# Precision_ATMega32U4_Copernicus.net
KiCad netlist of a schematic drawn in EAGLE
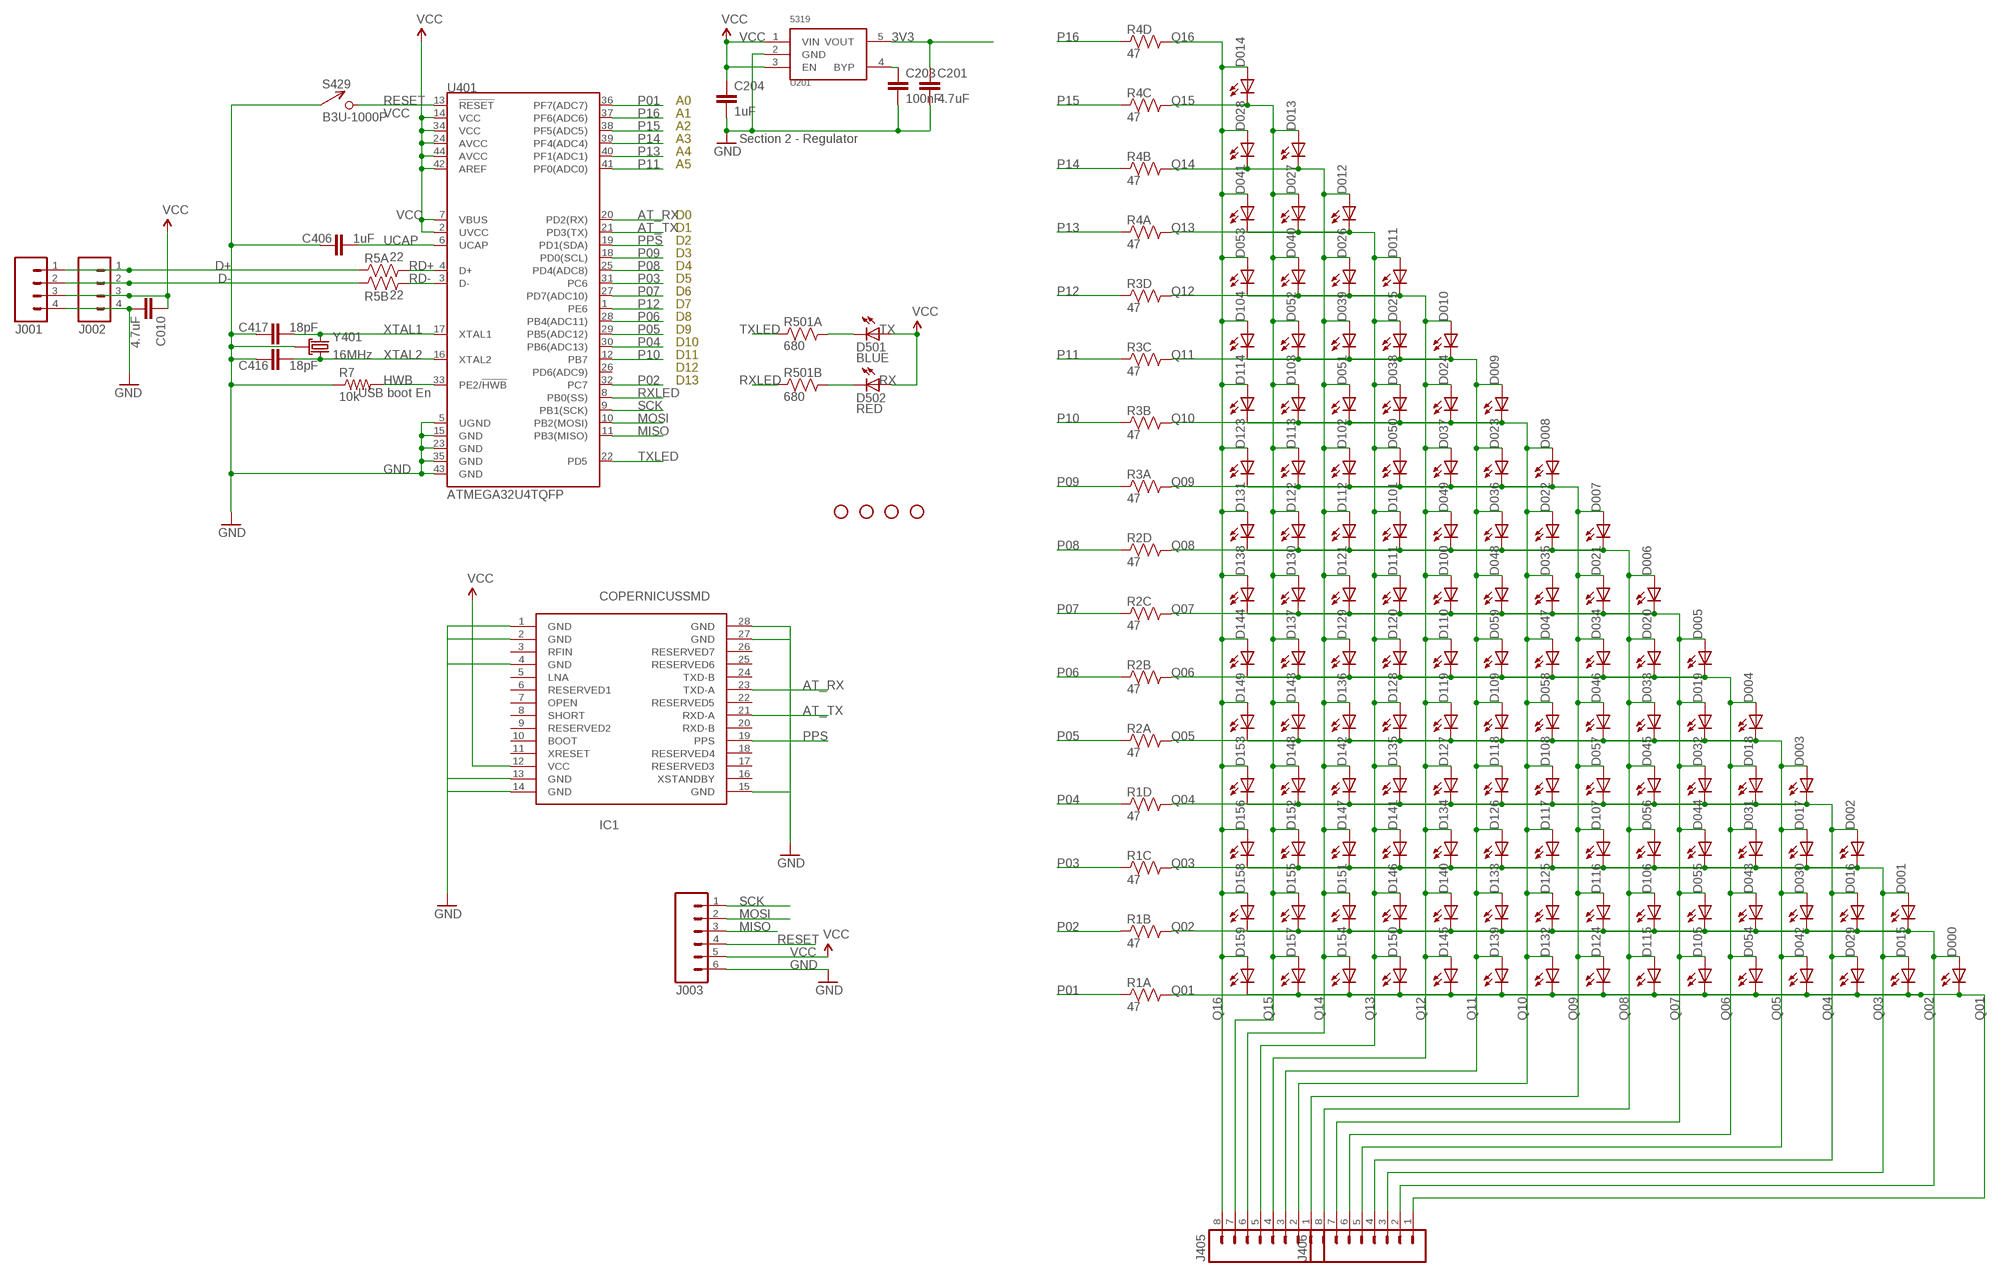
[diagram p0: schematic, sheet 1]

(export (version "E")
  (design (tool "Eeschema 10.0.6"))
  (components
    (comp (ref "C010")
      (value "4.7uF")
      (footprint "eagle-import:0603-CAP")
      (libsource (lib "eagle-import") (part "CAP0603-CAP"))
    )
    (comp (ref "C201")
      (value "4.7uF")
      (footprint "eagle-import:0402-CAP")
      (libsource (lib "eagle-import") (part "CAP0402-CAP"))
    )
    (comp (ref "C203")
      (value "100nF")
      (footprint "eagle-import:0402-CAP")
      (libsource (lib "eagle-import") (part "CAP0402-CAP"))
    )
    (comp (ref "C204")
      (value "1uF")
      (footprint "eagle-import:0402-CAP")
      (libsource (lib "eagle-import") (part "CAP0402-CAP"))
    )
    (comp (ref "C406")
      (value "1uF")
      (footprint "eagle-import:0603-CAP")
      (libsource (lib "eagle-import") (part "CAP0603-CAP"))
    )
    (comp (ref "C416")
      (value "18pF")
      (footprint "eagle-import:0603-CAP")
      (libsource (lib "eagle-import") (part "CAP0603-CAP"))
    )
    (comp (ref "C417")
      (value "18pF")
      (footprint "eagle-import:0603-CAP")
      (libsource (lib "eagle-import") (part "CAP0603-CAP"))
    )
    (comp (ref "D000")
      (value "HOUR")
      (footprint "eagle-import:LED-0603")
      (libsource (lib "eagle-import") (part "LED0603"))
    )
    (comp (ref "D001")
      (value "HOUR")
      (footprint "eagle-import:LED-0603")
      (libsource (lib "eagle-import") (part "LED0603"))
    )
    (comp (ref "D002")
      (value "HOUR")
      (footprint "eagle-import:LED-0603")
      (libsource (lib "eagle-import") (part "LED0603"))
    )
    (comp (ref "D003")
      (value "HOUR")
      (footprint "eagle-import:LED-0603")
      (libsource (lib "eagle-import") (part "LED0603"))
    )
    (comp (ref "D004")
      (value "HOUR")
      (footprint "eagle-import:LED-0603")
      (libsource (lib "eagle-import") (part "LED0603"))
    )
    (comp (ref "D005")
      (value "HOUR")
      (footprint "eagle-import:LED-0603")
      (libsource (lib "eagle-import") (part "LED0603"))
    )
    (comp (ref "D006")
      (value "HOUR")
      (footprint "eagle-import:LED-0603")
      (libsource (lib "eagle-import") (part "LED0603"))
    )
    (comp (ref "D007")
      (value "HOUR")
      (footprint "eagle-import:LED-0603")
      (libsource (lib "eagle-import") (part "LED0603"))
    )
    (comp (ref "D008")
      (value "HOUR")
      (footprint "eagle-import:LED-0603")
      (libsource (lib "eagle-import") (part "LED0603"))
    )
    (comp (ref "D009")
      (value "HOUR")
      (footprint "eagle-import:LED-0603")
      (libsource (lib "eagle-import") (part "LED0603"))
    )
    (comp (ref "D010")
      (value "HOUR")
      (footprint "eagle-import:LED-0603")
      (libsource (lib "eagle-import") (part "LED0603"))
    )
    (comp (ref "D011")
      (value "HOUR")
      (footprint "eagle-import:LED-0603")
      (libsource (lib "eagle-import") (part "LED0603"))
    )
    (comp (ref "D012")
      (value "HOUR")
      (footprint "eagle-import:LED-0603")
      (libsource (lib "eagle-import") (part "LED0603"))
    )
    (comp (ref "D013")
      (value "HOUR")
      (footprint "eagle-import:LED-0603")
      (libsource (lib "eagle-import") (part "LED0603"))
    )
    (comp (ref "D014")
      (value "HOUR")
      (footprint "eagle-import:LED-0603")
      (libsource (lib "eagle-import") (part "LED0603"))
    )
    (comp (ref "D015")
      (value "HOUR")
      (footprint "eagle-import:LED-0603")
      (libsource (lib "eagle-import") (part "LED0603"))
    )
    (comp (ref "D016")
      (value "HOUR")
      (footprint "eagle-import:LED-0603")
      (libsource (lib "eagle-import") (part "LED0603"))
    )
    (comp (ref "D017")
      (value "HOUR")
      (footprint "eagle-import:LED-0603")
      (libsource (lib "eagle-import") (part "LED0603"))
    )
    (comp (ref "D018")
      (value "HOUR")
      (footprint "eagle-import:LED-0603")
      (libsource (lib "eagle-import") (part "LED0603"))
    )
    (comp (ref "D019")
      (value "HOUR")
      (footprint "eagle-import:LED-0603")
      (libsource (lib "eagle-import") (part "LED0603"))
    )
    (comp (ref "D020")
      (value "HOUR")
      (footprint "eagle-import:LED-0603")
      (libsource (lib "eagle-import") (part "LED0603"))
    )
    (comp (ref "D021")
      (value "HOUR")
      (footprint "eagle-import:LED-0603")
      (libsource (lib "eagle-import") (part "LED0603"))
    )
    (comp (ref "D022")
      (value "HOUR")
      (footprint "eagle-import:LED-0603")
      (libsource (lib "eagle-import") (part "LED0603"))
    )
    (comp (ref "D023")
      (value "HOUR")
      (footprint "eagle-import:LED-0603")
      (libsource (lib "eagle-import") (part "LED0603"))
    )
    (comp (ref "D024")
      (value "HOUR")
      (footprint "eagle-import:LED-0603")
      (libsource (lib "eagle-import") (part "LED0603"))
    )
    (comp (ref "D025")
      (value "HOUR")
      (footprint "eagle-import:LED-0603")
      (libsource (lib "eagle-import") (part "LED0603"))
    )
    (comp (ref "D026")
      (value "HOUR")
      (footprint "eagle-import:LED-0603")
      (libsource (lib "eagle-import") (part "LED0603"))
    )
    (comp (ref "D027")
      (value "HOUR")
      (footprint "eagle-import:LED-0603")
      (libsource (lib "eagle-import") (part "LED0603"))
    )
    (comp (ref "D028")
      (value "HOUR")
      (footprint "eagle-import:LED-0603")
      (libsource (lib "eagle-import") (part "LED0603"))
    )
    (comp (ref "D029")
      (value "HOUR")
      (footprint "eagle-import:LED-0603")
      (libsource (lib "eagle-import") (part "LED0603"))
    )
    (comp (ref "D030")
      (value "HOUR")
      (footprint "eagle-import:LED-0603")
      (libsource (lib "eagle-import") (part "LED0603"))
    )
    (comp (ref "D031")
      (value "HOUR")
      (footprint "eagle-import:LED-0603")
      (libsource (lib "eagle-import") (part "LED0603"))
    )
    (comp (ref "D032")
      (value "HOUR")
      (footprint "eagle-import:LED-0603")
      (libsource (lib "eagle-import") (part "LED0603"))
    )
    (comp (ref "D033")
      (value "HOUR")
      (footprint "eagle-import:LED-0603")
      (libsource (lib "eagle-import") (part "LED0603"))
    )
    (comp (ref "D034")
      (value "HOUR")
      (footprint "eagle-import:LED-0603")
      (libsource (lib "eagle-import") (part "LED0603"))
    )
    (comp (ref "D035")
      (value "HOUR")
      (footprint "eagle-import:LED-0603")
      (libsource (lib "eagle-import") (part "LED0603"))
    )
    (comp (ref "D036")
      (value "HOUR")
      (footprint "eagle-import:LED-0603")
      (libsource (lib "eagle-import") (part "LED0603"))
    )
    (comp (ref "D037")
      (value "HOUR")
      (footprint "eagle-import:LED-0603")
      (libsource (lib "eagle-import") (part "LED0603"))
    )
    (comp (ref "D038")
      (value "HOUR")
      (footprint "eagle-import:LED-0603")
      (libsource (lib "eagle-import") (part "LED0603"))
    )
    (comp (ref "D039")
      (value "HOUR")
      (footprint "eagle-import:LED-0603")
      (libsource (lib "eagle-import") (part "LED0603"))
    )
    (comp (ref "D040")
      (value "HOUR")
      (footprint "eagle-import:LED-0603")
      (libsource (lib "eagle-import") (part "LED0603"))
    )
    (comp (ref "D041")
      (value "HOUR")
      (footprint "eagle-import:LED-0603")
      (libsource (lib "eagle-import") (part "LED0603"))
    )
    (comp (ref "D042")
      (value "HOUR")
      (footprint "eagle-import:LED-0603")
      (libsource (lib "eagle-import") (part "LED0603"))
    )
    (comp (ref "D043")
      (value "HOUR")
      (footprint "eagle-import:LED-0603")
      (libsource (lib "eagle-import") (part "LED0603"))
    )
    (comp (ref "D044")
      (value "HOUR")
      (footprint "eagle-import:LED-0603")
      (libsource (lib "eagle-import") (part "LED0603"))
    )
    (comp (ref "D045")
      (value "HOUR")
      (footprint "eagle-import:LED-0603")
      (libsource (lib "eagle-import") (part "LED0603"))
    )
    (comp (ref "D046")
      (value "HOUR")
      (footprint "eagle-import:LED-0603")
      (libsource (lib "eagle-import") (part "LED0603"))
    )
    (comp (ref "D047")
      (value "HOUR")
      (footprint "eagle-import:LED-0603")
      (libsource (lib "eagle-import") (part "LED0603"))
    )
    (comp (ref "D048")
      (value "HOUR")
      (footprint "eagle-import:LED-0603")
      (libsource (lib "eagle-import") (part "LED0603"))
    )
    (comp (ref "D049")
      (value "HOUR")
      (footprint "eagle-import:LED-0603")
      (libsource (lib "eagle-import") (part "LED0603"))
    )
    (comp (ref "D050")
      (value "HOUR")
      (footprint "eagle-import:LED-0603")
      (libsource (lib "eagle-import") (part "LED0603"))
    )
    (comp (ref "D051")
      (value "HOUR")
      (footprint "eagle-import:LED-0603")
      (libsource (lib "eagle-import") (part "LED0603"))
    )
    (comp (ref "D052")
      (value "HOUR")
      (footprint "eagle-import:LED-0603")
      (libsource (lib "eagle-import") (part "LED0603"))
    )
    (comp (ref "D053")
      (value "HOUR")
      (footprint "eagle-import:LED-0603")
      (libsource (lib "eagle-import") (part "LED0603"))
    )
    (comp (ref "D054")
      (value "HOUR")
      (footprint "eagle-import:LED-0603")
      (libsource (lib "eagle-import") (part "LED0603"))
    )
    (comp (ref "D055")
      (value "HOUR")
      (footprint "eagle-import:LED-0603")
      (libsource (lib "eagle-import") (part "LED0603"))
    )
    (comp (ref "D056")
      (value "HOUR")
      (footprint "eagle-import:LED-0603")
      (libsource (lib "eagle-import") (part "LED0603"))
    )
    (comp (ref "D057")
      (value "HOUR")
      (footprint "eagle-import:LED-0603")
      (libsource (lib "eagle-import") (part "LED0603"))
    )
    (comp (ref "D058")
      (value "HOUR")
      (footprint "eagle-import:LED-0603")
      (libsource (lib "eagle-import") (part "LED0603"))
    )
    (comp (ref "D059")
      (value "HOUR")
      (footprint "eagle-import:LED-0603")
      (libsource (lib "eagle-import") (part "LED0603"))
    )
    (comp (ref "D100")
      (value "HOUR")
      (footprint "eagle-import:LED-0603")
      (libsource (lib "eagle-import") (part "LED0603"))
    )
    (comp (ref "D101")
      (value "HOUR")
      (footprint "eagle-import:LED-0603")
      (libsource (lib "eagle-import") (part "LED0603"))
    )
    (comp (ref "D102")
      (value "HOUR")
      (footprint "eagle-import:LED-0603")
      (libsource (lib "eagle-import") (part "LED0603"))
    )
    (comp (ref "D103")
      (value "HOUR")
      (footprint "eagle-import:LED-0603")
      (libsource (lib "eagle-import") (part "LED0603"))
    )
    (comp (ref "D104")
      (value "HOUR")
      (footprint "eagle-import:LED-0603")
      (libsource (lib "eagle-import") (part "LED0603"))
    )
    (comp (ref "D105")
      (value "HOUR")
      (footprint "eagle-import:LED-0603")
      (libsource (lib "eagle-import") (part "LED0603"))
    )
    (comp (ref "D106")
      (value "HOUR")
      (footprint "eagle-import:LED-0603")
      (libsource (lib "eagle-import") (part "LED0603"))
    )
    (comp (ref "D107")
      (value "HOUR")
      (footprint "eagle-import:LED-0603")
      (libsource (lib "eagle-import") (part "LED0603"))
    )
    (comp (ref "D108")
      (value "HOUR")
      (footprint "eagle-import:LED-0603")
      (libsource (lib "eagle-import") (part "LED0603"))
    )
    (comp (ref "D109")
      (value "HOUR")
      (footprint "eagle-import:LED-0603")
      (libsource (lib "eagle-import") (part "LED0603"))
    )
    (comp (ref "D110")
      (value "HOUR")
      (footprint "eagle-import:LED-0603")
      (libsource (lib "eagle-import") (part "LED0603"))
    )
    (comp (ref "D111")
      (value "HOUR")
      (footprint "eagle-import:LED-0603")
      (libsource (lib "eagle-import") (part "LED0603"))
    )
    (comp (ref "D112")
      (value "HOUR")
      (footprint "eagle-import:LED-0603")
      (libsource (lib "eagle-import") (part "LED0603"))
    )
    (comp (ref "D113")
      (value "HOUR")
      (footprint "eagle-import:LED-0603")
      (libsource (lib "eagle-import") (part "LED0603"))
    )
    (comp (ref "D114")
      (value "HOUR")
      (footprint "eagle-import:LED-0603")
      (libsource (lib "eagle-import") (part "LED0603"))
    )
    (comp (ref "D115")
      (value "HOUR")
      (footprint "eagle-import:LED-0603")
      (libsource (lib "eagle-import") (part "LED0603"))
    )
    (comp (ref "D116")
      (value "HOUR")
      (footprint "eagle-import:LED-0603")
      (libsource (lib "eagle-import") (part "LED0603"))
    )
    (comp (ref "D117")
      (value "HOUR")
      (footprint "eagle-import:LED-0603")
      (libsource (lib "eagle-import") (part "LED0603"))
    )
    (comp (ref "D118")
      (value "HOUR")
      (footprint "eagle-import:LED-0603")
      (libsource (lib "eagle-import") (part "LED0603"))
    )
    (comp (ref "D119")
      (value "HOUR")
      (footprint "eagle-import:LED-0603")
      (libsource (lib "eagle-import") (part "LED0603"))
    )
    (comp (ref "D120")
      (value "HOUR")
      (footprint "eagle-import:LED-0603")
      (libsource (lib "eagle-import") (part "LED0603"))
    )
    (comp (ref "D121")
      (value "HOUR")
      (footprint "eagle-import:LED-0603")
      (libsource (lib "eagle-import") (part "LED0603"))
    )
    (comp (ref "D122")
      (value "HOUR")
      (footprint "eagle-import:LED-0603")
      (libsource (lib "eagle-import") (part "LED0603"))
    )
    (comp (ref "D123")
      (value "HOUR")
      (footprint "eagle-import:LED-0603")
      (libsource (lib "eagle-import") (part "LED0603"))
    )
    (comp (ref "D124")
      (value "HOUR")
      (footprint "eagle-import:LED-0603")
      (libsource (lib "eagle-import") (part "LED0603"))
    )
    (comp (ref "D125")
      (value "HOUR")
      (footprint "eagle-import:LED-0603")
      (libsource (lib "eagle-import") (part "LED0603"))
    )
    (comp (ref "D126")
      (value "HOUR")
      (footprint "eagle-import:LED-0603")
      (libsource (lib "eagle-import") (part "LED0603"))
    )
    (comp (ref "D127")
      (value "HOUR")
      (footprint "eagle-import:LED-0603")
      (libsource (lib "eagle-import") (part "LED0603"))
    )
    (comp (ref "D128")
      (value "HOUR")
      (footprint "eagle-import:LED-0603")
      (libsource (lib "eagle-import") (part "LED0603"))
    )
    (comp (ref "D129")
      (value "HOUR")
      (footprint "eagle-import:LED-0603")
      (libsource (lib "eagle-import") (part "LED0603"))
    )
    (comp (ref "D130")
      (value "HOUR")
      (footprint "eagle-import:LED-0603")
      (libsource (lib "eagle-import") (part "LED0603"))
    )
    (comp (ref "D131")
      (value "HOUR")
      (footprint "eagle-import:LED-0603")
      (libsource (lib "eagle-import") (part "LED0603"))
    )
    (comp (ref "D132")
      (value "HOUR")
      (footprint "eagle-import:LED-0603")
      (libsource (lib "eagle-import") (part "LED0603"))
    )
    (comp (ref "D133")
      (value "HOUR")
      (footprint "eagle-import:LED-0603")
      (libsource (lib "eagle-import") (part "LED0603"))
    )
    (comp (ref "D134")
      (value "HOUR")
      (footprint "eagle-import:LED-0603")
      (libsource (lib "eagle-import") (part "LED0603"))
    )
    (comp (ref "D135")
      (value "HOUR")
      (footprint "eagle-import:LED-0603")
      (libsource (lib "eagle-import") (part "LED0603"))
    )
    (comp (ref "D136")
      (value "HOUR")
      (footprint "eagle-import:LED-0603")
      (libsource (lib "eagle-import") (part "LED0603"))
    )
    (comp (ref "D137")
      (value "HOUR")
      (footprint "eagle-import:LED-0603")
      (libsource (lib "eagle-import") (part "LED0603"))
    )
    (comp (ref "D138")
      (value "HOUR")
      (footprint "eagle-import:LED-0603")
      (libsource (lib "eagle-import") (part "LED0603"))
    )
    (comp (ref "D139")
      (value "HOUR")
      (footprint "eagle-import:LED-0603")
      (libsource (lib "eagle-import") (part "LED0603"))
    )
    (comp (ref "D140")
      (value "HOUR")
      (footprint "eagle-import:LED-0603")
      (libsource (lib "eagle-import") (part "LED0603"))
    )
    (comp (ref "D141")
      (value "HOUR")
      (footprint "eagle-import:LED-0603")
      (libsource (lib "eagle-import") (part "LED0603"))
    )
    (comp (ref "D142")
      (value "HOUR")
      (footprint "eagle-import:LED-0603")
      (libsource (lib "eagle-import") (part "LED0603"))
    )
    (comp (ref "D143")
      (value "HOUR")
      (footprint "eagle-import:LED-0603")
      (libsource (lib "eagle-import") (part "LED0603"))
    )
    (comp (ref "D144")
      (value "HOUR")
      (footprint "eagle-import:LED-0603")
      (libsource (lib "eagle-import") (part "LED0603"))
    )
    (comp (ref "D145")
      (value "HOUR")
      (footprint "eagle-import:LED-0603")
      (libsource (lib "eagle-import") (part "LED0603"))
    )
    (comp (ref "D146")
      (value "HOUR")
      (footprint "eagle-import:LED-0603")
      (libsource (lib "eagle-import") (part "LED0603"))
    )
    (comp (ref "D147")
      (value "HOUR")
      (footprint "eagle-import:LED-0603")
      (libsource (lib "eagle-import") (part "LED0603"))
    )
    (comp (ref "D148")
      (value "HOUR")
      (footprint "eagle-import:LED-0603")
      (libsource (lib "eagle-import") (part "LED0603"))
    )
    (comp (ref "D149")
      (value "HOUR")
      (footprint "eagle-import:LED-0603")
      (libsource (lib "eagle-import") (part "LED0603"))
    )
    (comp (ref "D150")
      (value "HOUR")
      (footprint "eagle-import:LED-0603")
      (libsource (lib "eagle-import") (part "LED0603"))
    )
    (comp (ref "D151")
      (value "HOUR")
      (footprint "eagle-import:LED-0603")
      (libsource (lib "eagle-import") (part "LED0603"))
    )
    (comp (ref "D152")
      (value "HOUR")
      (footprint "eagle-import:LED-0603")
      (libsource (lib "eagle-import") (part "LED0603"))
    )
    (comp (ref "D153")
      (value "HOUR")
      (footprint "eagle-import:LED-0603")
      (libsource (lib "eagle-import") (part "LED0603"))
    )
    (comp (ref "D154")
      (value "HOUR")
      (footprint "eagle-import:LED-0603")
      (libsource (lib "eagle-import") (part "LED0603"))
    )
    (comp (ref "D155")
      (value "HOUR")
      (footprint "eagle-import:LED-0603")
      (libsource (lib "eagle-import") (part "LED0603"))
    )
    (comp (ref "D156")
      (value "HOUR")
      (footprint "eagle-import:LED-0603")
      (libsource (lib "eagle-import") (part "LED0603"))
    )
    (comp (ref "D157")
      (value "HOUR")
      (footprint "eagle-import:LED-0603")
      (libsource (lib "eagle-import") (part "LED0603"))
    )
    (comp (ref "D158")
      (value "HOUR")
      (footprint "eagle-import:LED-0603")
      (libsource (lib "eagle-import") (part "LED0603"))
    )
    (comp (ref "D159")
      (value "HOUR")
      (footprint "eagle-import:LED-0603")
      (libsource (lib "eagle-import") (part "LED0603"))
    )
    (comp (ref "D501")
      (value "BLUE")
      (footprint "eagle-import:LED-0603")
      (libsource (lib "eagle-import") (part "LED0603"))
    )
    (comp (ref "D502")
      (value "RED")
      (footprint "eagle-import:LED-0603")
      (libsource (lib "eagle-import") (part "LED0603"))
    )
    (comp (ref "IC1")
      (value "COPERNICUSSMD")
      (footprint "eagle-import:COPERNICUS")
      (libsource (lib "eagle-import") (part "COPERNICUSSMD"))
    )
    (comp (ref "J001")
      (value "M04PTH")
      (footprint "eagle-import:1X04")
      (libsource (lib "eagle-import") (part "M04PTH"))
    )
    (comp (ref "J002")
      (value "M04PTH")
      (footprint "eagle-import:1X04")
      (libsource (lib "eagle-import") (part "M04PTH"))
    )
    (comp (ref "J003")
      (value "M06SIP")
      (footprint "eagle-import:1X06")
      (libsource (lib "eagle-import") (part "M06SIP"))
    )
    (comp (ref "J405")
      (value "M081X08")
      (footprint "eagle-import:1X08")
      (libsource (lib "eagle-import") (part "M081X08"))
    )
    (comp (ref "J406")
      (value "M081X08")
      (footprint "eagle-import:1X08")
      (libsource (lib "eagle-import") (part "M081X08"))
    )
    (comp (ref "JP1")
      (value "STAND-OFF")
      (footprint "eagle-import:STAND-OFF")
      (libsource (lib "eagle-import") (part "STAND-OFF"))
    )
    (comp (ref "JP2")
      (value "STAND-OFF")
      (footprint "eagle-import:STAND-OFF")
      (libsource (lib "eagle-import") (part "STAND-OFF"))
    )
    (comp (ref "JP3")
      (value "STAND-OFF")
      (footprint "eagle-import:STAND-OFF")
      (libsource (lib "eagle-import") (part "STAND-OFF"))
    )
    (comp (ref "JP4")
      (value "STAND-OFF")
      (footprint "eagle-import:STAND-OFF")
      (libsource (lib "eagle-import") (part "STAND-OFF"))
    )
    (comp (ref "R1")
      (value "47")
      (footprint "eagle-import:CRA04")
      (libsource (lib "eagle-import") (part "RP404"))
    )
    (comp (ref "R2")
      (value "47")
      (footprint "eagle-import:CRA04")
      (libsource (lib "eagle-import") (part "RP404"))
    )
    (comp (ref "R3")
      (value "47")
      (footprint "eagle-import:CRA04")
      (libsource (lib "eagle-import") (part "RP404"))
    )
    (comp (ref "R4")
      (value "47")
      (footprint "eagle-import:CRA04")
      (libsource (lib "eagle-import") (part "RP404"))
    )
    (comp (ref "R5")
      (value "22")
      (footprint "eagle-import:CRA02")
      (libsource (lib "eagle-import") (part "RP2EXB24V"))
    )
    (comp (ref "R7")
      (value "10k")
      (footprint "eagle-import:0603-RES")
      (libsource (lib "eagle-import") (part "RESISTOR0603-RES"))
    )
    (comp (ref "R501")
      (value "680")
      (footprint "eagle-import:CRA02")
      (libsource (lib "eagle-import") (part "RP2EXB24V"))
    )
    (comp (ref "S429")
      (value "B3U-1000P")
      (footprint "eagle-import:B3U-1000P")
      (libsource (lib "eagle-import") (part "B3U-1000P"))
    )
    (comp (ref "U201")
      (value "5319")
      (footprint "eagle-import:SOT-23-5")
      (libsource (lib "eagle-import") (part "MIC5319D5"))
    )
    (comp (ref "U401")
      (value "ATMEGA32U4TQFP")
      (footprint "eagle-import:SPARKFUN-DIGITALIC_TQFP44")
      (libsource (lib "eagle-import") (part "ATMEGA32U4TQFP"))
    )
    (comp (ref "Y401")
      (value "16MHz")
      (footprint "eagle-import:CRYSTAL_SMD")
      (libsource (lib "eagle-import") (part "TSX-3225"))
    )
  )
  (nets
    (net (code "1") (name "/3V3") (class "Default")
      (node (ref "C201") (pin "1") (pinfunction "1_1") (pintype "passive"))
      (node (ref "U201") (pin "5") (pinfunction "VOUT_5") (pintype "bidirectional"))
    )
    (net (code "2") (name "/AT_RX") (class "Default")
      (node (ref "IC1") (pin "23") (pinfunction "TXD-A_23") (pintype "bidirectional"))
      (node (ref "U401") (pin "20") (pinfunction "PD2(RX)_20") (pintype "bidirectional"))
    )
    (net (code "3") (name "/AT_TX") (class "Default")
      (node (ref "IC1") (pin "21") (pinfunction "RXD-A_21") (pintype "bidirectional"))
      (node (ref "U401") (pin "21") (pinfunction "PD3(TX)_21") (pintype "bidirectional"))
    )
    (net (code "4") (name "/D+") (class "Default")
      (node (ref "J001") (pin "1") (pinfunction "1_1") (pintype "passive"))
      (node (ref "J002") (pin "1") (pinfunction "1_1") (pintype "passive"))
      (node (ref "R5") (pin "1") (pinfunction "1_1") (pintype "passive"))
    )
    (net (code "5") (name "/D-") (class "Default")
      (node (ref "J001") (pin "2") (pinfunction "2_2") (pintype "passive"))
      (node (ref "J002") (pin "2") (pinfunction "2_2") (pintype "passive"))
      (node (ref "R5") (pin "2") (pinfunction "1_2") (pintype "passive"))
    )
    (net (code "6") (name "/HWB") (class "Default")
      (node (ref "R7") (pin "2") (pinfunction "2_2") (pintype "passive"))
      (node (ref "U401") (pin "33") (pinfunction "PE2/~{HWB}_33") (pintype "bidirectional"))
    )
    (net (code "7") (name "/MISO") (class "Default")
      (node (ref "J003") (pin "3") (pinfunction "3_3") (pintype "passive"))
      (node (ref "U401") (pin "11") (pinfunction "PB3(MISO)_11") (pintype "bidirectional"))
    )
    (net (code "8") (name "/MOSI") (class "Default")
      (node (ref "J003") (pin "2") (pinfunction "2_2") (pintype "passive"))
      (node (ref "U401") (pin "10") (pinfunction "PB2(MOSI)_10") (pintype "bidirectional"))
    )
    (net (code "9") (name "/P01") (class "Default")
      (node (ref "R1") (pin "1") (pinfunction "1_1") (pintype "passive"))
      (node (ref "U401") (pin "36") (pinfunction "PF7(ADC7)_36") (pintype "bidirectional"))
    )
    (net (code "10") (name "/P02") (class "Default")
      (node (ref "R1") (pin "2") (pinfunction "1_2") (pintype "passive"))
      (node (ref "U401") (pin "32") (pinfunction "PC7_32") (pintype "bidirectional"))
    )
    (net (code "11") (name "/P03") (class "Default")
      (node (ref "R1") (pin "3") (pinfunction "1_3") (pintype "passive"))
      (node (ref "U401") (pin "31") (pinfunction "PC6_31") (pintype "bidirectional"))
    )
    (net (code "12") (name "/P04") (class "Default")
      (node (ref "R1") (pin "4") (pinfunction "1_4") (pintype "passive"))
      (node (ref "U401") (pin "30") (pinfunction "PB6(ADC13)_30") (pintype "bidirectional"))
    )
    (net (code "13") (name "/P05") (class "Default")
      (node (ref "R2") (pin "1") (pinfunction "1_1") (pintype "passive"))
      (node (ref "U401") (pin "29") (pinfunction "PB5(ADC12)_29") (pintype "bidirectional"))
    )
    (net (code "14") (name "/P06") (class "Default")
      (node (ref "R2") (pin "2") (pinfunction "1_2") (pintype "passive"))
      (node (ref "U401") (pin "28") (pinfunction "PB4(ADC11)_28") (pintype "bidirectional"))
    )
    (net (code "15") (name "/P07") (class "Default")
      (node (ref "R2") (pin "3") (pinfunction "1_3") (pintype "passive"))
      (node (ref "U401") (pin "27") (pinfunction "PD7(ADC10)_27") (pintype "bidirectional"))
    )
    (net (code "16") (name "/P08") (class "Default")
      (node (ref "R2") (pin "4") (pinfunction "1_4") (pintype "passive"))
      (node (ref "U401") (pin "25") (pinfunction "PD4(ADC8)_25") (pintype "bidirectional"))
    )
    (net (code "17") (name "/P09") (class "Default")
      (node (ref "R3") (pin "1") (pinfunction "1_1") (pintype "passive"))
      (node (ref "U401") (pin "18") (pinfunction "PD0(SCL)_18") (pintype "bidirectional"))
    )
    (net (code "18") (name "/P10") (class "Default")
      (node (ref "R3") (pin "2") (pinfunction "1_2") (pintype "passive"))
      (node (ref "U401") (pin "12") (pinfunction "PB7_12") (pintype "bidirectional"))
    )
    (net (code "19") (name "/P11") (class "Default")
      (node (ref "R3") (pin "3") (pinfunction "1_3") (pintype "passive"))
      (node (ref "U401") (pin "41") (pinfunction "PF0(ADC0)_41") (pintype "bidirectional"))
    )
    (net (code "20") (name "/P12") (class "Default")
      (node (ref "R3") (pin "4") (pinfunction "1_4") (pintype "passive"))
      (node (ref "U401") (pin "1") (pinfunction "PE6_1") (pintype "bidirectional"))
    )
    (net (code "21") (name "/P13") (class "Default")
      (node (ref "R4") (pin "1") (pinfunction "1_1") (pintype "passive"))
      (node (ref "U401") (pin "40") (pinfunction "PF1(ADC1)_40") (pintype "bidirectional"))
    )
    (net (code "22") (name "/P14") (class "Default")
      (node (ref "R4") (pin "2") (pinfunction "1_2") (pintype "passive"))
      (node (ref "U401") (pin "39") (pinfunction "PF4(ADC4)_39") (pintype "bidirectional"))
    )
    (net (code "23") (name "/P15") (class "Default")
      (node (ref "R4") (pin "3") (pinfunction "1_3") (pintype "passive"))
      (node (ref "U401") (pin "38") (pinfunction "PF5(ADC5)_38") (pintype "bidirectional"))
    )
    (net (code "24") (name "/P16") (class "Default")
      (node (ref "R4") (pin "4") (pinfunction "1_4") (pintype "passive"))
      (node (ref "U401") (pin "37") (pinfunction "PF6(ADC6)_37") (pintype "bidirectional"))
    )
    (net (code "25") (name "/PPS") (class "Default")
      (node (ref "IC1") (pin "19") (pinfunction "PPS_19") (pintype "bidirectional"))
      (node (ref "U401") (pin "19") (pinfunction "PD1(SDA)_19") (pintype "bidirectional"))
    )
    (net (code "26") (name "/Q01") (class "Default")
      (node (ref "D000") (pin "C") (pinfunction "C_C") (pintype "passive"))
      (node (ref "D015") (pin "C") (pinfunction "C_C") (pintype "passive"))
      (node (ref "D029") (pin "C") (pinfunction "C_C") (pintype "passive"))
      (node (ref "D042") (pin "C") (pinfunction "C_C") (pintype "passive"))
      (node (ref "D054") (pin "C") (pinfunction "C_C") (pintype "passive"))
      (node (ref "D105") (pin "C") (pinfunction "C_C") (pintype "passive"))
      (node (ref "D115") (pin "C") (pinfunction "C_C") (pintype "passive"))
      (node (ref "D124") (pin "C") (pinfunction "C_C") (pintype "passive"))
      (node (ref "D132") (pin "C") (pinfunction "C_C") (pintype "passive"))
      (node (ref "D139") (pin "C") (pinfunction "C_C") (pintype "passive"))
      (node (ref "D145") (pin "C") (pinfunction "C_C") (pintype "passive"))
      (node (ref "D150") (pin "C") (pinfunction "C_C") (pintype "passive"))
      (node (ref "D154") (pin "C") (pinfunction "C_C") (pintype "passive"))
      (node (ref "D157") (pin "C") (pinfunction "C_C") (pintype "passive"))
      (node (ref "D159") (pin "C") (pinfunction "C_C") (pintype "passive"))
      (node (ref "J406") (pin "1") (pinfunction "1_1") (pintype "passive"))
      (node (ref "R1") (pin "8") (pinfunction "2_8") (pintype "passive"))
    )
    (net (code "27") (name "/Q02") (class "Default")
      (node (ref "D000") (pin "A") (pinfunction "A_A") (pintype "passive"))
      (node (ref "D001") (pin "C") (pinfunction "C_C") (pintype "passive"))
      (node (ref "D016") (pin "C") (pinfunction "C_C") (pintype "passive"))
      (node (ref "D030") (pin "C") (pinfunction "C_C") (pintype "passive"))
      (node (ref "D043") (pin "C") (pinfunction "C_C") (pintype "passive"))
      (node (ref "D055") (pin "C") (pinfunction "C_C") (pintype "passive"))
      (node (ref "D106") (pin "C") (pinfunction "C_C") (pintype "passive"))
      (node (ref "D116") (pin "C") (pinfunction "C_C") (pintype "passive"))
      (node (ref "D125") (pin "C") (pinfunction "C_C") (pintype "passive"))
      (node (ref "D133") (pin "C") (pinfunction "C_C") (pintype "passive"))
      (node (ref "D140") (pin "C") (pinfunction "C_C") (pintype "passive"))
      (node (ref "D146") (pin "C") (pinfunction "C_C") (pintype "passive"))
      (node (ref "D151") (pin "C") (pinfunction "C_C") (pintype "passive"))
      (node (ref "D155") (pin "C") (pinfunction "C_C") (pintype "passive"))
      (node (ref "D158") (pin "C") (pinfunction "C_C") (pintype "passive"))
      (node (ref "J406") (pin "2") (pinfunction "2_2") (pintype "passive"))
      (node (ref "R1") (pin "7") (pinfunction "2_7") (pintype "passive"))
    )
    (net (code "28") (name "/Q03") (class "Default")
      (node (ref "D001") (pin "A") (pinfunction "A_A") (pintype "passive"))
      (node (ref "D002") (pin "C") (pinfunction "C_C") (pintype "passive"))
      (node (ref "D015") (pin "A") (pinfunction "A_A") (pintype "passive"))
      (node (ref "D017") (pin "C") (pinfunction "C_C") (pintype "passive"))
      (node (ref "D031") (pin "C") (pinfunction "C_C") (pintype "passive"))
      (node (ref "D044") (pin "C") (pinfunction "C_C") (pintype "passive"))
      (node (ref "D056") (pin "C") (pinfunction "C_C") (pintype "passive"))
      (node (ref "D107") (pin "C") (pinfunction "C_C") (pintype "passive"))
      (node (ref "D117") (pin "C") (pinfunction "C_C") (pintype "passive"))
      (node (ref "D126") (pin "C") (pinfunction "C_C") (pintype "passive"))
      (node (ref "D134") (pin "C") (pinfunction "C_C") (pintype "passive"))
      (node (ref "D141") (pin "C") (pinfunction "C_C") (pintype "passive"))
      (node (ref "D147") (pin "C") (pinfunction "C_C") (pintype "passive"))
      (node (ref "D152") (pin "C") (pinfunction "C_C") (pintype "passive"))
      (node (ref "D156") (pin "C") (pinfunction "C_C") (pintype "passive"))
      (node (ref "J406") (pin "3") (pinfunction "3_3") (pintype "passive"))
      (node (ref "R1") (pin "6") (pinfunction "2_6") (pintype "passive"))
    )
    (net (code "29") (name "/Q04") (class "Default")
      (node (ref "D002") (pin "A") (pinfunction "A_A") (pintype "passive"))
      (node (ref "D003") (pin "C") (pinfunction "C_C") (pintype "passive"))
      (node (ref "D016") (pin "A") (pinfunction "A_A") (pintype "passive"))
      (node (ref "D018") (pin "C") (pinfunction "C_C") (pintype "passive"))
      (node (ref "D029") (pin "A") (pinfunction "A_A") (pintype "passive"))
      (node (ref "D032") (pin "C") (pinfunction "C_C") (pintype "passive"))
      (node (ref "D045") (pin "C") (pinfunction "C_C") (pintype "passive"))
      (node (ref "D057") (pin "C") (pinfunction "C_C") (pintype "passive"))
      (node (ref "D108") (pin "C") (pinfunction "C_C") (pintype "passive"))
      (node (ref "D118") (pin "C") (pinfunction "C_C") (pintype "passive"))
      (node (ref "D127") (pin "C") (pinfunction "C_C") (pintype "passive"))
      (node (ref "D135") (pin "C") (pinfunction "C_C") (pintype "passive"))
      (node (ref "D142") (pin "C") (pinfunction "C_C") (pintype "passive"))
      (node (ref "D148") (pin "C") (pinfunction "C_C") (pintype "passive"))
      (node (ref "D153") (pin "C") (pinfunction "C_C") (pintype "passive"))
      (node (ref "J406") (pin "4") (pinfunction "4_4") (pintype "passive"))
      (node (ref "R1") (pin "5") (pinfunction "2_5") (pintype "passive"))
    )
    (net (code "30") (name "/Q05") (class "Default")
      (node (ref "D003") (pin "A") (pinfunction "A_A") (pintype "passive"))
      (node (ref "D004") (pin "C") (pinfunction "C_C") (pintype "passive"))
      (node (ref "D017") (pin "A") (pinfunction "A_A") (pintype "passive"))
      (node (ref "D019") (pin "C") (pinfunction "C_C") (pintype "passive"))
      (node (ref "D030") (pin "A") (pinfunction "A_A") (pintype "passive"))
      (node (ref "D033") (pin "C") (pinfunction "C_C") (pintype "passive"))
      (node (ref "D042") (pin "A") (pinfunction "A_A") (pintype "passive"))
      (node (ref "D046") (pin "C") (pinfunction "C_C") (pintype "passive"))
      (node (ref "D058") (pin "C") (pinfunction "C_C") (pintype "passive"))
      (node (ref "D109") (pin "C") (pinfunction "C_C") (pintype "passive"))
      (node (ref "D119") (pin "C") (pinfunction "C_C") (pintype "passive"))
      (node (ref "D128") (pin "C") (pinfunction "C_C") (pintype "passive"))
      (node (ref "D136") (pin "C") (pinfunction "C_C") (pintype "passive"))
      (node (ref "D143") (pin "C") (pinfunction "C_C") (pintype "passive"))
      (node (ref "D149") (pin "C") (pinfunction "C_C") (pintype "passive"))
      (node (ref "J406") (pin "5") (pinfunction "5_5") (pintype "passive"))
      (node (ref "R2") (pin "8") (pinfunction "2_8") (pintype "passive"))
    )
    (net (code "31") (name "/Q06") (class "Default")
      (node (ref "D004") (pin "A") (pinfunction "A_A") (pintype "passive"))
      (node (ref "D005") (pin "C") (pinfunction "C_C") (pintype "passive"))
      (node (ref "D018") (pin "A") (pinfunction "A_A") (pintype "passive"))
      (node (ref "D020") (pin "C") (pinfunction "C_C") (pintype "passive"))
      (node (ref "D031") (pin "A") (pinfunction "A_A") (pintype "passive"))
      (node (ref "D034") (pin "C") (pinfunction "C_C") (pintype "passive"))
      (node (ref "D043") (pin "A") (pinfunction "A_A") (pintype "passive"))
      (node (ref "D047") (pin "C") (pinfunction "C_C") (pintype "passive"))
      (node (ref "D054") (pin "A") (pinfunction "A_A") (pintype "passive"))
      (node (ref "D059") (pin "C") (pinfunction "C_C") (pintype "passive"))
      (node (ref "D110") (pin "C") (pinfunction "C_C") (pintype "passive"))
      (node (ref "D120") (pin "C") (pinfunction "C_C") (pintype "passive"))
      (node (ref "D129") (pin "C") (pinfunction "C_C") (pintype "passive"))
      (node (ref "D137") (pin "C") (pinfunction "C_C") (pintype "passive"))
      (node (ref "D144") (pin "C") (pinfunction "C_C") (pintype "passive"))
      (node (ref "J406") (pin "6") (pinfunction "6_6") (pintype "passive"))
      (node (ref "R2") (pin "7") (pinfunction "2_7") (pintype "passive"))
    )
    (net (code "32") (name "/Q07") (class "Default")
      (node (ref "D005") (pin "A") (pinfunction "A_A") (pintype "passive"))
      (node (ref "D006") (pin "C") (pinfunction "C_C") (pintype "passive"))
      (node (ref "D019") (pin "A") (pinfunction "A_A") (pintype "passive"))
      (node (ref "D021") (pin "C") (pinfunction "C_C") (pintype "passive"))
      (node (ref "D032") (pin "A") (pinfunction "A_A") (pintype "passive"))
      (node (ref "D035") (pin "C") (pinfunction "C_C") (pintype "passive"))
      (node (ref "D044") (pin "A") (pinfunction "A_A") (pintype "passive"))
      (node (ref "D048") (pin "C") (pinfunction "C_C") (pintype "passive"))
      (node (ref "D055") (pin "A") (pinfunction "A_A") (pintype "passive"))
      (node (ref "D100") (pin "C") (pinfunction "C_C") (pintype "passive"))
      (node (ref "D105") (pin "A") (pinfunction "A_A") (pintype "passive"))
      (node (ref "D111") (pin "C") (pinfunction "C_C") (pintype "passive"))
      (node (ref "D121") (pin "C") (pinfunction "C_C") (pintype "passive"))
      (node (ref "D130") (pin "C") (pinfunction "C_C") (pintype "passive"))
      (node (ref "D138") (pin "C") (pinfunction "C_C") (pintype "passive"))
      (node (ref "J406") (pin "7") (pinfunction "7_7") (pintype "passive"))
      (node (ref "R2") (pin "6") (pinfunction "2_6") (pintype "passive"))
    )
    (net (code "33") (name "/Q08") (class "Default")
      (node (ref "D006") (pin "A") (pinfunction "A_A") (pintype "passive"))
      (node (ref "D007") (pin "C") (pinfunction "C_C") (pintype "passive"))
      (node (ref "D020") (pin "A") (pinfunction "A_A") (pintype "passive"))
      (node (ref "D022") (pin "C") (pinfunction "C_C") (pintype "passive"))
      (node (ref "D033") (pin "A") (pinfunction "A_A") (pintype "passive"))
      (node (ref "D036") (pin "C") (pinfunction "C_C") (pintype "passive"))
      (node (ref "D045") (pin "A") (pinfunction "A_A") (pintype "passive"))
      (node (ref "D049") (pin "C") (pinfunction "C_C") (pintype "passive"))
      (node (ref "D056") (pin "A") (pinfunction "A_A") (pintype "passive"))
      (node (ref "D101") (pin "C") (pinfunction "C_C") (pintype "passive"))
      (node (ref "D106") (pin "A") (pinfunction "A_A") (pintype "passive"))
      (node (ref "D112") (pin "C") (pinfunction "C_C") (pintype "passive"))
      (node (ref "D115") (pin "A") (pinfunction "A_A") (pintype "passive"))
      (node (ref "D122") (pin "C") (pinfunction "C_C") (pintype "passive"))
      (node (ref "D131") (pin "C") (pinfunction "C_C") (pintype "passive"))
      (node (ref "J406") (pin "8") (pinfunction "8_8") (pintype "passive"))
      (node (ref "R2") (pin "5") (pinfunction "2_5") (pintype "passive"))
    )
    (net (code "34") (name "/Q09") (class "Default")
      (node (ref "D007") (pin "A") (pinfunction "A_A") (pintype "passive"))
      (node (ref "D008") (pin "C") (pinfunction "C_C") (pintype "passive"))
      (node (ref "D021") (pin "A") (pinfunction "A_A") (pintype "passive"))
      (node (ref "D023") (pin "C") (pinfunction "C_C") (pintype "passive"))
      (node (ref "D034") (pin "A") (pinfunction "A_A") (pintype "passive"))
      (node (ref "D037") (pin "C") (pinfunction "C_C") (pintype "passive"))
      (node (ref "D046") (pin "A") (pinfunction "A_A") (pintype "passive"))
      (node (ref "D050") (pin "C") (pinfunction "C_C") (pintype "passive"))
      (node (ref "D057") (pin "A") (pinfunction "A_A") (pintype "passive"))
      (node (ref "D102") (pin "C") (pinfunction "C_C") (pintype "passive"))
      (node (ref "D107") (pin "A") (pinfunction "A_A") (pintype "passive"))
      (node (ref "D113") (pin "C") (pinfunction "C_C") (pintype "passive"))
      (node (ref "D116") (pin "A") (pinfunction "A_A") (pintype "passive"))
      (node (ref "D123") (pin "C") (pinfunction "C_C") (pintype "passive"))
      (node (ref "D124") (pin "A") (pinfunction "A_A") (pintype "passive"))
      (node (ref "J405") (pin "1") (pinfunction "1_1") (pintype "passive"))
      (node (ref "R3") (pin "8") (pinfunction "2_8") (pintype "passive"))
    )
    (net (code "35") (name "/Q10") (class "Default")
      (node (ref "D008") (pin "A") (pinfunction "A_A") (pintype "passive"))
      (node (ref "D009") (pin "C") (pinfunction "C_C") (pintype "passive"))
      (node (ref "D022") (pin "A") (pinfunction "A_A") (pintype "passive"))
      (node (ref "D024") (pin "C") (pinfunction "C_C") (pintype "passive"))
      (node (ref "D035") (pin "A") (pinfunction "A_A") (pintype "passive"))
      (node (ref "D038") (pin "C") (pinfunction "C_C") (pintype "passive"))
      (node (ref "D047") (pin "A") (pinfunction "A_A") (pintype "passive"))
      (node (ref "D051") (pin "C") (pinfunction "C_C") (pintype "passive"))
      (node (ref "D058") (pin "A") (pinfunction "A_A") (pintype "passive"))
      (node (ref "D103") (pin "C") (pinfunction "C_C") (pintype "passive"))
      (node (ref "D108") (pin "A") (pinfunction "A_A") (pintype "passive"))
      (node (ref "D114") (pin "C") (pinfunction "C_C") (pintype "passive"))
      (node (ref "D117") (pin "A") (pinfunction "A_A") (pintype "passive"))
      (node (ref "D125") (pin "A") (pinfunction "A_A") (pintype "passive"))
      (node (ref "D132") (pin "A") (pinfunction "A_A") (pintype "passive"))
      (node (ref "J405") (pin "2") (pinfunction "2_2") (pintype "passive"))
      (node (ref "R3") (pin "7") (pinfunction "2_7") (pintype "passive"))
    )
    (net (code "36") (name "/Q11") (class "Default")
      (node (ref "D009") (pin "A") (pinfunction "A_A") (pintype "passive"))
      (node (ref "D010") (pin "C") (pinfunction "C_C") (pintype "passive"))
      (node (ref "D023") (pin "A") (pinfunction "A_A") (pintype "passive"))
      (node (ref "D025") (pin "C") (pinfunction "C_C") (pintype "passive"))
      (node (ref "D036") (pin "A") (pinfunction "A_A") (pintype "passive"))
      (node (ref "D039") (pin "C") (pinfunction "C_C") (pintype "passive"))
      (node (ref "D048") (pin "A") (pinfunction "A_A") (pintype "passive"))
      (node (ref "D052") (pin "C") (pinfunction "C_C") (pintype "passive"))
      (node (ref "D059") (pin "A") (pinfunction "A_A") (pintype "passive"))
      (node (ref "D104") (pin "C") (pinfunction "C_C") (pintype "passive"))
      (node (ref "D109") (pin "A") (pinfunction "A_A") (pintype "passive"))
      (node (ref "D118") (pin "A") (pinfunction "A_A") (pintype "passive"))
      (node (ref "D126") (pin "A") (pinfunction "A_A") (pintype "passive"))
      (node (ref "D133") (pin "A") (pinfunction "A_A") (pintype "passive"))
      (node (ref "D139") (pin "A") (pinfunction "A_A") (pintype "passive"))
      (node (ref "J405") (pin "3") (pinfunction "3_3") (pintype "passive"))
      (node (ref "R3") (pin "6") (pinfunction "2_6") (pintype "passive"))
    )
    (net (code "37") (name "/Q12") (class "Default")
      (node (ref "D010") (pin "A") (pinfunction "A_A") (pintype "passive"))
      (node (ref "D011") (pin "C") (pinfunction "C_C") (pintype "passive"))
      (node (ref "D024") (pin "A") (pinfunction "A_A") (pintype "passive"))
      (node (ref "D026") (pin "C") (pinfunction "C_C") (pintype "passive"))
      (node (ref "D037") (pin "A") (pinfunction "A_A") (pintype "passive"))
      (node (ref "D040") (pin "C") (pinfunction "C_C") (pintype "passive"))
      (node (ref "D049") (pin "A") (pinfunction "A_A") (pintype "passive"))
      (node (ref "D053") (pin "C") (pinfunction "C_C") (pintype "passive"))
      (node (ref "D100") (pin "A") (pinfunction "A_A") (pintype "passive"))
      (node (ref "D110") (pin "A") (pinfunction "A_A") (pintype "passive"))
      (node (ref "D119") (pin "A") (pinfunction "A_A") (pintype "passive"))
      (node (ref "D127") (pin "A") (pinfunction "A_A") (pintype "passive"))
      (node (ref "D134") (pin "A") (pinfunction "A_A") (pintype "passive"))
      (node (ref "D140") (pin "A") (pinfunction "A_A") (pintype "passive"))
      (node (ref "D145") (pin "A") (pinfunction "A_A") (pintype "passive"))
      (node (ref "J405") (pin "4") (pinfunction "4_4") (pintype "passive"))
      (node (ref "R3") (pin "5") (pinfunction "2_5") (pintype "passive"))
    )
    (net (code "38") (name "/Q13") (class "Default")
      (node (ref "D011") (pin "A") (pinfunction "A_A") (pintype "passive"))
      (node (ref "D012") (pin "C") (pinfunction "C_C") (pintype "passive"))
      (node (ref "D025") (pin "A") (pinfunction "A_A") (pintype "passive"))
      (node (ref "D027") (pin "C") (pinfunction "C_C") (pintype "passive"))
      (node (ref "D038") (pin "A") (pinfunction "A_A") (pintype "passive"))
      (node (ref "D041") (pin "C") (pinfunction "C_C") (pintype "passive"))
      (node (ref "D050") (pin "A") (pinfunction "A_A") (pintype "passive"))
      (node (ref "D101") (pin "A") (pinfunction "A_A") (pintype "passive"))
      (node (ref "D111") (pin "A") (pinfunction "A_A") (pintype "passive"))
      (node (ref "D120") (pin "A") (pinfunction "A_A") (pintype "passive"))
      (node (ref "D128") (pin "A") (pinfunction "A_A") (pintype "passive"))
      (node (ref "D135") (pin "A") (pinfunction "A_A") (pintype "passive"))
      (node (ref "D141") (pin "A") (pinfunction "A_A") (pintype "passive"))
      (node (ref "D146") (pin "A") (pinfunction "A_A") (pintype "passive"))
      (node (ref "D150") (pin "A") (pinfunction "A_A") (pintype "passive"))
      (node (ref "J405") (pin "5") (pinfunction "5_5") (pintype "passive"))
      (node (ref "R4") (pin "8") (pinfunction "2_8") (pintype "passive"))
    )
    (net (code "39") (name "/Q14") (class "Default")
      (node (ref "D012") (pin "A") (pinfunction "A_A") (pintype "passive"))
      (node (ref "D013") (pin "C") (pinfunction "C_C") (pintype "passive"))
      (node (ref "D026") (pin "A") (pinfunction "A_A") (pintype "passive"))
      (node (ref "D028") (pin "C") (pinfunction "C_C") (pintype "passive"))
      (node (ref "D039") (pin "A") (pinfunction "A_A") (pintype "passive"))
      (node (ref "D051") (pin "A") (pinfunction "A_A") (pintype "passive"))
      (node (ref "D102") (pin "A") (pinfunction "A_A") (pintype "passive"))
      (node (ref "D112") (pin "A") (pinfunction "A_A") (pintype "passive"))
      (node (ref "D121") (pin "A") (pinfunction "A_A") (pintype "passive"))
      (node (ref "D129") (pin "A") (pinfunction "A_A") (pintype "passive"))
      (node (ref "D136") (pin "A") (pinfunction "A_A") (pintype "passive"))
      (node (ref "D142") (pin "A") (pinfunction "A_A") (pintype "passive"))
      (node (ref "D147") (pin "A") (pinfunction "A_A") (pintype "passive"))
      (node (ref "D151") (pin "A") (pinfunction "A_A") (pintype "passive"))
      (node (ref "D154") (pin "A") (pinfunction "A_A") (pintype "passive"))
      (node (ref "J405") (pin "6") (pinfunction "6_6") (pintype "passive"))
      (node (ref "R4") (pin "7") (pinfunction "2_7") (pintype "passive"))
    )
    (net (code "40") (name "/Q15") (class "Default")
      (node (ref "D013") (pin "A") (pinfunction "A_A") (pintype "passive"))
      (node (ref "D014") (pin "C") (pinfunction "C_C") (pintype "passive"))
      (node (ref "D027") (pin "A") (pinfunction "A_A") (pintype "passive"))
      (node (ref "D040") (pin "A") (pinfunction "A_A") (pintype "passive"))
      (node (ref "D052") (pin "A") (pinfunction "A_A") (pintype "passive"))
      (node (ref "D103") (pin "A") (pinfunction "A_A") (pintype "passive"))
      (node (ref "D113") (pin "A") (pinfunction "A_A") (pintype "passive"))
      (node (ref "D122") (pin "A") (pinfunction "A_A") (pintype "passive"))
      (node (ref "D130") (pin "A") (pinfunction "A_A") (pintype "passive"))
      (node (ref "D137") (pin "A") (pinfunction "A_A") (pintype "passive"))
      (node (ref "D143") (pin "A") (pinfunction "A_A") (pintype "passive"))
      (node (ref "D148") (pin "A") (pinfunction "A_A") (pintype "passive"))
      (node (ref "D152") (pin "A") (pinfunction "A_A") (pintype "passive"))
      (node (ref "D155") (pin "A") (pinfunction "A_A") (pintype "passive"))
      (node (ref "D157") (pin "A") (pinfunction "A_A") (pintype "passive"))
      (node (ref "J405") (pin "7") (pinfunction "7_7") (pintype "passive"))
      (node (ref "R4") (pin "6") (pinfunction "2_6") (pintype "passive"))
    )
    (net (code "41") (name "/Q16") (class "Default")
      (node (ref "D014") (pin "A") (pinfunction "A_A") (pintype "passive"))
      (node (ref "D028") (pin "A") (pinfunction "A_A") (pintype "passive"))
      (node (ref "D041") (pin "A") (pinfunction "A_A") (pintype "passive"))
      (node (ref "D053") (pin "A") (pinfunction "A_A") (pintype "passive"))
      (node (ref "D104") (pin "A") (pinfunction "A_A") (pintype "passive"))
      (node (ref "D114") (pin "A") (pinfunction "A_A") (pintype "passive"))
      (node (ref "D123") (pin "A") (pinfunction "A_A") (pintype "passive"))
      (node (ref "D131") (pin "A") (pinfunction "A_A") (pintype "passive"))
      (node (ref "D138") (pin "A") (pinfunction "A_A") (pintype "passive"))
      (node (ref "D144") (pin "A") (pinfunction "A_A") (pintype "passive"))
      (node (ref "D149") (pin "A") (pinfunction "A_A") (pintype "passive"))
      (node (ref "D153") (pin "A") (pinfunction "A_A") (pintype "passive"))
      (node (ref "D156") (pin "A") (pinfunction "A_A") (pintype "passive"))
      (node (ref "D158") (pin "A") (pinfunction "A_A") (pintype "passive"))
      (node (ref "D159") (pin "A") (pinfunction "A_A") (pintype "passive"))
      (node (ref "J405") (pin "8") (pinfunction "8_8") (pintype "passive"))
      (node (ref "R4") (pin "5") (pinfunction "2_5") (pintype "passive"))
    )
    (net (code "42") (name "/RD+") (class "Default")
      (node (ref "R5") (pin "4") (pinfunction "2_4") (pintype "passive"))
      (node (ref "U401") (pin "4") (pinfunction "D+_4") (pintype "bidirectional"))
    )
    (net (code "43") (name "/RD-") (class "Default")
      (node (ref "R5") (pin "3") (pinfunction "2_3") (pintype "passive"))
      (node (ref "U401") (pin "3") (pinfunction "D-_3") (pintype "bidirectional"))
    )
    (net (code "44") (name "/RESET") (class "Default")
      (node (ref "J003") (pin "4") (pinfunction "4_4") (pintype "passive"))
      (node (ref "S429") (pin "P$2") (pinfunction "2_P$2") (pintype "bidirectional"))
      (node (ref "U401") (pin "13") (pinfunction "~{RESET}_13") (pintype "bidirectional"))
    )
    (net (code "45") (name "/RXLED") (class "Default")
      (node (ref "R501") (pin "2") (pinfunction "1_2") (pintype "passive"))
      (node (ref "U401") (pin "8") (pinfunction "PB0(SS)_8") (pintype "bidirectional"))
    )
    (net (code "46") (name "/SCK") (class "Default")
      (node (ref "J003") (pin "1") (pinfunction "1_1") (pintype "passive"))
      (node (ref "U401") (pin "9") (pinfunction "PB1(SCK)_9") (pintype "bidirectional"))
    )
    (net (code "47") (name "/TXLED") (class "Default")
      (node (ref "R501") (pin "1") (pinfunction "1_1") (pintype "passive"))
      (node (ref "U401") (pin "22") (pinfunction "PD5_22") (pintype "bidirectional"))
    )
    (net (code "48") (name "/UCAP") (class "Default")
      (node (ref "C406") (pin "1") (pinfunction "1_1") (pintype "passive"))
      (node (ref "U401") (pin "6") (pinfunction "UCAP_6") (pintype "bidirectional"))
    )
    (net (code "49") (name "/XTAL1") (class "Default")
      (node (ref "C417") (pin "2") (pinfunction "2_2") (pintype "passive"))
      (node (ref "U401") (pin "17") (pinfunction "XTAL1_17") (pintype "bidirectional"))
      (node (ref "Y401") (pin "1") (pinfunction "1_1") (pintype "passive"))
    )
    (net (code "50") (name "/XTAL2") (class "Default")
      (node (ref "C416") (pin "2") (pinfunction "2_2") (pintype "passive"))
      (node (ref "U401") (pin "16") (pinfunction "XTAL2_16") (pintype "bidirectional"))
      (node (ref "Y401") (pin "3") (pinfunction "2_3") (pintype "passive"))
    )
    (net (code "51") (name "GND") (class "Default")
      (node (ref "C010") (pin "2") (pinfunction "2_2") (pintype "passive"))
      (node (ref "C201") (pin "2") (pinfunction "2_2") (pintype "passive"))
      (node (ref "C203") (pin "2") (pinfunction "2_2") (pintype "passive"))
      (node (ref "C204") (pin "2") (pinfunction "2_2") (pintype "passive"))
      (node (ref "C406") (pin "2") (pinfunction "2_2") (pintype "passive"))
      (node (ref "C416") (pin "1") (pinfunction "1_1") (pintype "passive"))
      (node (ref "C417") (pin "1") (pinfunction "1_1") (pintype "passive"))
      (node (ref "IC1") (pin "1") (pinfunction "GND_1") (pintype "bidirectional"))
      (node (ref "IC1") (pin "13") (pinfunction "GND_13") (pintype "bidirectional"))
      (node (ref "IC1") (pin "14") (pinfunction "GND_14") (pintype "bidirectional"))
      (node (ref "IC1") (pin "15") (pinfunction "GND_15") (pintype "bidirectional"))
      (node (ref "IC1") (pin "2") (pinfunction "GND_2") (pintype "bidirectional"))
      (node (ref "IC1") (pin "27") (pinfunction "GND_27") (pintype "bidirectional"))
      (node (ref "IC1") (pin "28") (pinfunction "GND_28") (pintype "bidirectional"))
      (node (ref "IC1") (pin "4") (pinfunction "GND_4") (pintype "bidirectional"))
      (node (ref "J001") (pin "4") (pinfunction "4_4") (pintype "passive"))
      (node (ref "J002") (pin "4") (pinfunction "4_4") (pintype "passive"))
      (node (ref "J003") (pin "6") (pinfunction "6_6") (pintype "passive"))
      (node (ref "R7") (pin "1") (pinfunction "1_1") (pintype "passive"))
      (node (ref "S429") (pin "P$1") (pinfunction "1_P$1") (pintype "bidirectional"))
      (node (ref "U201") (pin "2") (pinfunction "GND_2") (pintype "bidirectional"))
      (node (ref "U401") (pin "15") (pinfunction "GND_15") (pintype "bidirectional"))
      (node (ref "U401") (pin "23") (pinfunction "GND_23") (pintype "bidirectional"))
      (node (ref "U401") (pin "35") (pinfunction "GND_35") (pintype "bidirectional"))
      (node (ref "U401") (pin "43") (pinfunction "GND_43") (pintype "bidirectional"))
      (node (ref "U401") (pin "5") (pinfunction "UGND_5") (pintype "bidirectional"))
      (node (ref "Y401") (pin "2") (pinfunction "GND_2") (pintype "passive"))
      (node (ref "Y401") (pin "4") (pinfunction "GND_4") (pintype "passive"))
    )
    (net (code "52") (name "Net-(R501A-2)") (class "Default")
      (node (ref "D501") (pin "C") (pinfunction "C_C") (pintype "passive"))
      (node (ref "R501") (pin "4") (pinfunction "2_4") (pintype "passive"))
    )
    (net (code "53") (name "Net-(R501B-2)") (class "Default")
      (node (ref "D502") (pin "C") (pinfunction "C_C") (pintype "passive"))
      (node (ref "R501") (pin "3") (pinfunction "2_3") (pintype "passive"))
    )
    (net (code "54") (name "Net-(U201-BYP)") (class "Default")
      (node (ref "C203") (pin "1") (pinfunction "1_1") (pintype "passive"))
      (node (ref "U201") (pin "4") (pinfunction "BYP_4") (pintype "bidirectional"))
    )
    (net (code "55") (name "VCC") (class "Default")
      (node (ref "C010") (pin "1") (pinfunction "1_1") (pintype "passive"))
      (node (ref "C204") (pin "1") (pinfunction "1_1") (pintype "passive"))
      (node (ref "D501") (pin "A") (pinfunction "A_A") (pintype "passive"))
      (node (ref "D502") (pin "A") (pinfunction "A_A") (pintype "passive"))
      (node (ref "IC1") (pin "12") (pinfunction "VCC_12") (pintype "bidirectional"))
      (node (ref "J001") (pin "3") (pinfunction "3_3") (pintype "passive"))
      (node (ref "J002") (pin "3") (pinfunction "3_3") (pintype "passive"))
      (node (ref "J003") (pin "5") (pinfunction "5_5") (pintype "passive"))
      (node (ref "U201") (pin "1") (pinfunction "VIN_1") (pintype "bidirectional"))
      (node (ref "U201") (pin "3") (pinfunction "EN_3") (pintype "bidirectional"))
      (node (ref "U401") (pin "14") (pinfunction "VCC_14") (pintype "bidirectional"))
      (node (ref "U401") (pin "2") (pinfunction "UVCC_2") (pintype "bidirectional"))
      (node (ref "U401") (pin "24") (pinfunction "AVCC_24") (pintype "bidirectional"))
      (node (ref "U401") (pin "34") (pinfunction "VCC_34") (pintype "bidirectional"))
      (node (ref "U401") (pin "42") (pinfunction "AREF_42") (pintype "bidirectional"))
      (node (ref "U401") (pin "44") (pinfunction "AVCC_44") (pintype "bidirectional"))
      (node (ref "U401") (pin "7") (pinfunction "VBUS_7") (pintype "bidirectional"))
    )
    (net (code "56") (name "unconnected-(IC1-BOOT-Pad10)") (class "Default")
      (node (ref "IC1") (pin "10") (pinfunction "BOOT_10") (pintype "bidirectional"))
    )
    (net (code "57") (name "unconnected-(IC1-LNA-Pad5)") (class "Default")
      (node (ref "IC1") (pin "5") (pinfunction "LNA_5") (pintype "bidirectional"))
    )
    (net (code "58") (name "unconnected-(IC1-OPEN-Pad7)") (class "Default")
      (node (ref "IC1") (pin "7") (pinfunction "OPEN_7") (pintype "bidirectional"))
    )
    (net (code "59") (name "unconnected-(IC1-RESERVED1-Pad6)") (class "Default")
      (node (ref "IC1") (pin "6") (pinfunction "RESERVED1_6") (pintype "bidirectional"))
    )
    (net (code "60") (name "unconnected-(IC1-RESERVED2-Pad9)") (class "Default")
      (node (ref "IC1") (pin "9") (pinfunction "RESERVED2_9") (pintype "bidirectional"))
    )
    (net (code "61") (name "unconnected-(IC1-RESERVED3-Pad17)") (class "Default")
      (node (ref "IC1") (pin "17") (pinfunction "RESERVED3_17") (pintype "bidirectional"))
    )
    (net (code "62") (name "unconnected-(IC1-RESERVED4-Pad18)") (class "Default")
      (node (ref "IC1") (pin "18") (pinfunction "RESERVED4_18") (pintype "bidirectional"))
    )
    (net (code "63") (name "unconnected-(IC1-RESERVED5-Pad22)") (class "Default")
      (node (ref "IC1") (pin "22") (pinfunction "RESERVED5_22") (pintype "bidirectional"))
    )
    (net (code "64") (name "unconnected-(IC1-RESERVED6-Pad25)") (class "Default")
      (node (ref "IC1") (pin "25") (pinfunction "RESERVED6_25") (pintype "bidirectional"))
    )
    (net (code "65") (name "unconnected-(IC1-RESERVED7-Pad26)") (class "Default")
      (node (ref "IC1") (pin "26") (pinfunction "RESERVED7_26") (pintype "bidirectional"))
    )
    (net (code "66") (name "unconnected-(IC1-RFIN-Pad3)") (class "Default")
      (node (ref "IC1") (pin "3") (pinfunction "RFIN_3") (pintype "bidirectional"))
    )
    (net (code "67") (name "unconnected-(IC1-RXD-B-Pad20)") (class "Default")
      (node (ref "IC1") (pin "20") (pinfunction "RXD-B_20") (pintype "bidirectional"))
    )
    (net (code "68") (name "unconnected-(IC1-SHORT-Pad8)") (class "Default")
      (node (ref "IC1") (pin "8") (pinfunction "SHORT_8") (pintype "bidirectional"))
    )
    (net (code "69") (name "unconnected-(IC1-TXD-B-Pad24)") (class "Default")
      (node (ref "IC1") (pin "24") (pinfunction "TXD-B_24") (pintype "bidirectional"))
    )
    (net (code "70") (name "unconnected-(IC1-XRESET-Pad11)") (class "Default")
      (node (ref "IC1") (pin "11") (pinfunction "XRESET_11") (pintype "bidirectional"))
    )
    (net (code "71") (name "unconnected-(IC1-XSTANDBY-Pad16)") (class "Default")
      (node (ref "IC1") (pin "16") (pinfunction "XSTANDBY_16") (pintype "bidirectional"))
    )
    (net (code "72") (name "unconnected-(U401-PD6(ADC9)-Pad26)") (class "Default")
      (node (ref "U401") (pin "26") (pinfunction "PD6(ADC9)_26") (pintype "bidirectional"))
    )
  )
)
